# EspDetElet.net
KiCad netlist of a schematic drawn in EAGLE
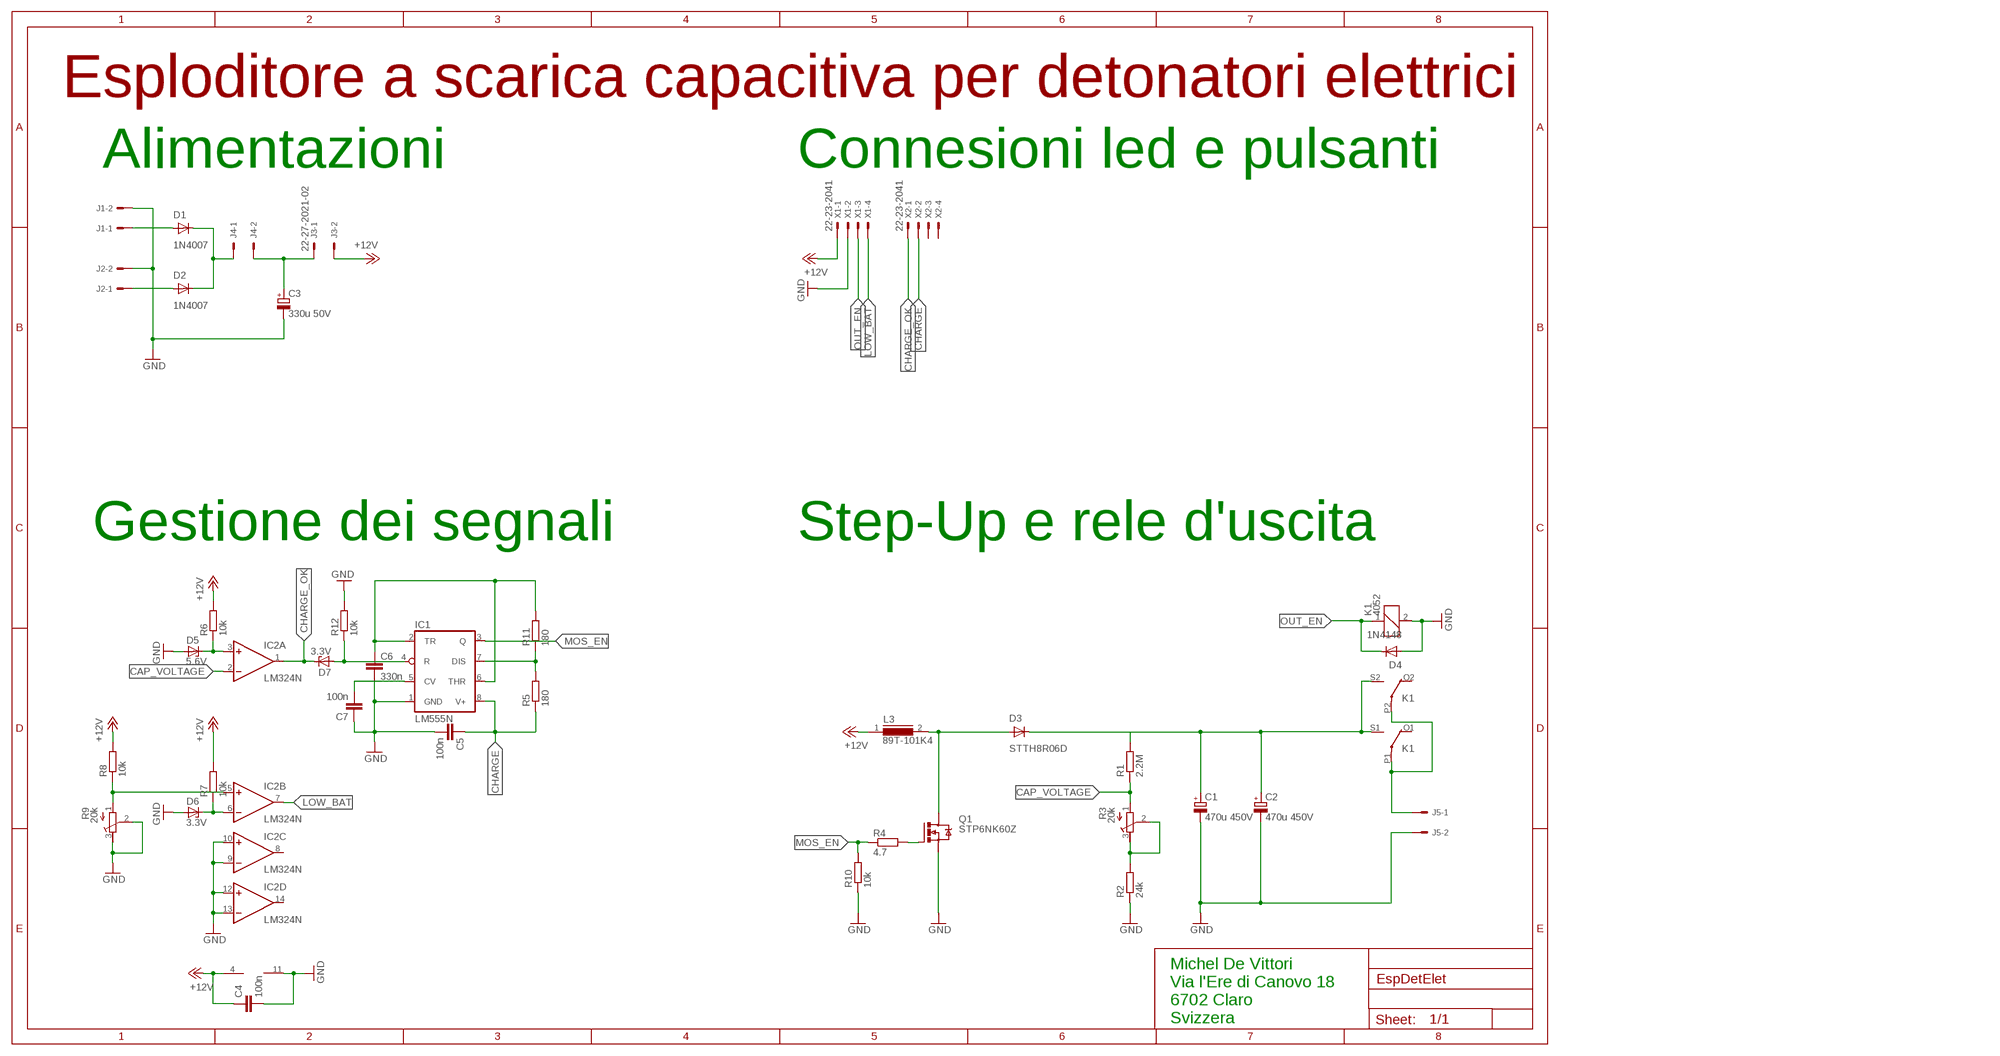
[diagram p0: schematic, sheet 1]

(export (version "E")
  (design (tool "Eeschema 10.0.6"))
  (components
    (comp (ref "C1")
      (value "470u 450V")
      (footprint "eagle-import:EB30D")
      (libsource (lib "eagle-import") (part "CPOL-EUE10-30"))
    )
    (comp (ref "C2")
      (value "470u 450V")
      (footprint "eagle-import:EB30D")
      (libsource (lib "eagle-import") (part "CPOL-EUE10-30"))
    )
    (comp (ref "C3")
      (value "330u 50V")
      (footprint "eagle-import:E5-10,5")
      (libsource (lib "eagle-import") (part "CPOL-EUE5-10.5"))
    )
    (comp (ref "C4")
      (value "100n")
      (footprint "eagle-import:C025-025X050")
      (libsource (lib "eagle-import") (part "C-EU025-025X050"))
    )
    (comp (ref "C5")
      (value "100n")
      (footprint "eagle-import:C025-025X050")
      (libsource (lib "eagle-import") (part "C-EU025-025X050"))
    )
    (comp (ref "C6")
      (value "330n")
      (footprint "eagle-import:C050-030X075")
      (libsource (lib "eagle-import") (part "C-EU050-030X075"))
    )
    (comp (ref "C7")
      (value "100n")
      (footprint "eagle-import:C025-025X050")
      (libsource (lib "eagle-import") (part "C-EU025-025X050"))
    )
    (comp (ref "D1")
      (value "1N4007")
      (footprint "eagle-import:DO41-10")
      (libsource (lib "eagle-import") (part "1N4004"))
    )
    (comp (ref "D2")
      (value "1N4007")
      (footprint "eagle-import:DO41-10")
      (libsource (lib "eagle-import") (part "1N4004"))
    )
    (comp (ref "D3")
      (value "STTH8R06D")
      (footprint "eagle-import:TO220ACS")
      (libsource (lib "eagle-import") (part "BYT08P"))
    )
    (comp (ref "D4")
      (value "1N4148")
      (footprint "eagle-import:DO35-7")
      (libsource (lib "eagle-import") (part "1N4148DO35-7"))
    )
    (comp (ref "D5")
      (value "5.6V")
      (footprint "eagle-import:ZDIO-7.5")
      (libsource (lib "eagle-import") (part "ZENER-DIODEZD-7.5"))
    )
    (comp (ref "D6")
      (value "3.3V")
      (footprint "eagle-import:ZDIO-7.5")
      (libsource (lib "eagle-import") (part "ZENER-DIODEZD-7.5"))
    )
    (comp (ref "D7")
      (value "3.3V")
      (footprint "eagle-import:ZDIO-7.5")
      (libsource (lib "eagle-import") (part "ZENER-DIODEZD-7.5"))
    )
    (comp (ref "IC1")
      (value "LM555N")
      (footprint "eagle-import:DIL08")
      (libsource (lib "eagle-import") (part "555NLM"))
    )
    (comp (ref "IC2")
      (value "LM324N")
      (footprint "eagle-import:DIL14")
      (libsource (lib "eagle-import") (part "LM324N"))
    )
    (comp (ref "J1")
      (value "KK-156-2")
      (footprint "eagle-import:KK-156-2")
      (libsource (lib "eagle-import") (part "KK-156-2"))
    )
    (comp (ref "J2")
      (value "KK-156-2")
      (footprint "eagle-import:KK-156-2")
      (libsource (lib "eagle-import") (part "KK-156-2"))
    )
    (comp (ref "J3")
      (value "22-27-2021-02")
      (footprint "eagle-import:6410-02")
      (libsource (lib "eagle-import") (part "22-?-0227-2021"))
    )
    (comp (ref "J4")
      (value "KK-156-2")
      (footprint "eagle-import:KK-156-2")
      (libsource (lib "eagle-import") (part "KK-156-2"))
    )
    (comp (ref "J5")
      (value "KK-156-2")
      (footprint "eagle-import:KK-156-2")
      (libsource (lib "eagle-import") (part "KK-156-2"))
    )
    (comp (ref "K1")
      (value "4052")
      (footprint "eagle-import:F4052")
      (libsource (lib "eagle-import") (part "4052"))
    )
    (comp (ref "L3")
      (value "89T-101K4")
      (footprint "eagle-import:SFT1030")
      (libsource (lib "eagle-import") (part "SFT1030"))
    )
    (comp (ref "Q1")
      (value "STP6NK60Z")
      (footprint "eagle-import:TO220BV")
      (libsource (lib "eagle-import") (part "STP5NA50"))
    )
    (comp (ref "R1")
      (value "2.2M")
      (footprint "eagle-import:0207_10")
      (libsource (lib "eagle-import") (part "R-EU_0207/10"))
    )
    (comp (ref "R2")
      (value "24k")
      (footprint "eagle-import:0207_10")
      (libsource (lib "eagle-import") (part "R-EU_0207/10"))
    )
    (comp (ref "R3")
      (value "20k")
      (footprint "eagle-import:RTRIM64W")
      (libsource (lib "eagle-import") (part "R-TRIMM64W"))
    )
    (comp (ref "R4")
      (value "4.7")
      (footprint "eagle-import:0207_10")
      (libsource (lib "eagle-import") (part "R-EU_0207/10"))
    )
    (comp (ref "R5")
      (value "180")
      (footprint "eagle-import:0207_10")
      (libsource (lib "eagle-import") (part "R-EU_0207/10"))
    )
    (comp (ref "R6")
      (value "10k")
      (footprint "eagle-import:0207_10")
      (libsource (lib "eagle-import") (part "R-EU_0207/10"))
    )
    (comp (ref "R7")
      (value "10k")
      (footprint "eagle-import:0207_10")
      (libsource (lib "eagle-import") (part "R-EU_0207/10"))
    )
    (comp (ref "R8")
      (value "10k")
      (footprint "eagle-import:0207_10")
      (libsource (lib "eagle-import") (part "R-EU_0207/10"))
    )
    (comp (ref "R9")
      (value "20k")
      (footprint "eagle-import:RTRIM64W")
      (libsource (lib "eagle-import") (part "R-TRIMM64W"))
    )
    (comp (ref "R10")
      (value "10k")
      (footprint "eagle-import:0207_10")
      (libsource (lib "eagle-import") (part "R-EU_0207/10"))
    )
    (comp (ref "R11")
      (value "180")
      (footprint "eagle-import:0207_10")
      (libsource (lib "eagle-import") (part "R-EU_0207/10"))
    )
    (comp (ref "R12")
      (value "10k")
      (footprint "eagle-import:0207_10")
      (libsource (lib "eagle-import") (part "R-EU_0207/10"))
    )
    (comp (ref "X1")
      (value "22-23-2041")
      (footprint "eagle-import:22-23-2041")
      (fields (field (name "MF") "MOLEX"))
      (libsource (lib "eagle-import") (part "22-23-2041"))
    )
    (comp (ref "X2")
      (value "22-23-2041")
      (footprint "eagle-import:22-23-2041")
      (fields (field (name "MF") "MOLEX"))
      (libsource (lib "eagle-import") (part "22-23-2041"))
    )
  )
  (nets
    (net (code "1") (name "+12V") (class "Default")
      (node (ref "C4") (pin "1") (pinfunction "1_1") (pintype "passive"))
      (node (ref "IC2") (pin "4") (pinfunction "V+_4") (pintype "power_in"))
      (node (ref "J3") (pin "2") (pinfunction "S_2") (pintype "passive"))
      (node (ref "L3") (pin "1") (pinfunction "1_1") (pintype "passive"))
      (node (ref "R6") (pin "2") (pinfunction "2_2") (pintype "passive"))
      (node (ref "R7") (pin "2") (pinfunction "2_2") (pintype "passive"))
      (node (ref "R8") (pin "2") (pinfunction "2_2") (pintype "passive"))
      (node (ref "X1") (pin "1") (pinfunction "S_1") (pintype "passive"))
    )
    (net (code "2") (name "CAP_VOLTAGE") (class "Default")
      (node (ref "IC2") (pin "2") (pinfunction "-IN_2") (pintype "input"))
      (node (ref "R1") (pin "1") (pinfunction "1_1") (pintype "passive"))
      (node (ref "R3") (pin "1") (pinfunction "E_1") (pintype "passive"))
    )
    (net (code "3") (name "CHARGE") (class "Default")
      (node (ref "C5") (pin "1") (pinfunction "1_1") (pintype "passive"))
      (node (ref "IC1") (pin "8") (pinfunction "V+_8") (pintype "power_in"))
      (node (ref "R5") (pin "1") (pinfunction "1_1") (pintype "passive"))
      (node (ref "X2") (pin "2") (pinfunction "S_2") (pintype "passive"))
    )
    (net (code "4") (name "CHARGE_OK") (class "Default")
      (node (ref "D7") (pin "C") (pinfunction "C_C") (pintype "passive"))
      (node (ref "IC2") (pin "1") (pinfunction "OUT_1") (pintype "output"))
      (node (ref "X2") (pin "1") (pinfunction "S_1") (pintype "passive"))
    )
    (net (code "5") (name "GND") (class "Default")
      (node (ref "C1") (pin "-") (pinfunction "-_-") (pintype "passive"))
      (node (ref "C2") (pin "-") (pinfunction "-_-") (pintype "passive"))
      (node (ref "C3") (pin "-") (pinfunction "-_-") (pintype "passive"))
      (node (ref "C4") (pin "2") (pinfunction "2_2") (pintype "passive"))
      (node (ref "C5") (pin "2") (pinfunction "2_2") (pintype "passive"))
      (node (ref "C6") (pin "2") (pinfunction "2_2") (pintype "passive"))
      (node (ref "C7") (pin "1") (pinfunction "1_1") (pintype "passive"))
      (node (ref "D4") (pin "A") (pinfunction "A_A") (pintype "passive"))
      (node (ref "D5") (pin "A") (pinfunction "A_A") (pintype "passive"))
      (node (ref "D6") (pin "A") (pinfunction "A_A") (pintype "passive"))
      (node (ref "IC1") (pin "1") (pinfunction "GND_1") (pintype "power_in"))
      (node (ref "IC2") (pin "10") (pinfunction "+IN_10") (pintype "input"))
      (node (ref "IC2") (pin "11") (pinfunction "V-_11") (pintype "power_in"))
      (node (ref "IC2") (pin "12") (pinfunction "+IN_12") (pintype "input"))
      (node (ref "IC2") (pin "13") (pinfunction "-IN_13") (pintype "input"))
      (node (ref "IC2") (pin "9") (pinfunction "-IN_9") (pintype "input"))
      (node (ref "J1") (pin "2") (pinfunction "S_2") (pintype "passive"))
      (node (ref "J2") (pin "2") (pinfunction "S_2") (pintype "passive"))
      (node (ref "J5") (pin "2") (pinfunction "S_2") (pintype "passive"))
      (node (ref "K1") (pin "2") (pinfunction "2_2") (pintype "passive"))
      (node (ref "Q1") (pin "S") (pinfunction "S_S") (pintype "passive"))
      (node (ref "R10") (pin "1") (pinfunction "1_1") (pintype "passive"))
      (node (ref "R12") (pin "2") (pinfunction "2_2") (pintype "passive"))
      (node (ref "R2") (pin "1") (pinfunction "1_1") (pintype "passive"))
      (node (ref "R9") (pin "2") (pinfunction "S_2") (pintype "passive"))
      (node (ref "R9") (pin "3") (pinfunction "A_3") (pintype "passive"))
      (node (ref "X1") (pin "2") (pinfunction "S_2") (pintype "passive"))
    )
    (net (code "6") (name "LOW_BAT") (class "Default")
      (node (ref "IC2") (pin "7") (pinfunction "OUT_7") (pintype "output"))
      (node (ref "X1") (pin "4") (pinfunction "S_4") (pintype "passive"))
    )
    (net (code "7") (name "MOS_EN") (class "Default")
      (node (ref "IC1") (pin "3") (pinfunction "Q_3") (pintype "output"))
      (node (ref "R10") (pin "2") (pinfunction "2_2") (pintype "passive"))
      (node (ref "R4") (pin "1") (pinfunction "1_1") (pintype "passive"))
    )
    (net (code "8") (name "Net-(D3-PadA)") (class "Default")
      (node (ref "D3") (pin "A") (pinfunction "A_A") (pintype "passive"))
      (node (ref "L3") (pin "2") (pinfunction "2_2") (pintype "passive"))
      (node (ref "Q1") (pin "D") (pinfunction "D_D") (pintype "passive"))
    )
    (net (code "9") (name "Net-(IC1-CV)") (class "Default")
      (node (ref "C7") (pin "2") (pinfunction "2_2") (pintype "passive"))
      (node (ref "IC1") (pin "5") (pinfunction "CV_5") (pintype "input"))
    )
    (net (code "10") (name "Net-(IC1-DIS)") (class "Default")
      (node (ref "IC1") (pin "7") (pinfunction "DIS_7") (pintype "input"))
      (node (ref "R11") (pin "1") (pinfunction "1_1") (pintype "passive"))
      (node (ref "R5") (pin "2") (pinfunction "2_2") (pintype "passive"))
    )
    (net (code "11") (name "Net-(IC1-R)") (class "Default")
      (node (ref "D7") (pin "A") (pinfunction "A_A") (pintype "passive"))
      (node (ref "IC1") (pin "4") (pinfunction "R_4") (pintype "input"))
      (node (ref "R12") (pin "1") (pinfunction "1_1") (pintype "passive"))
    )
    (net (code "12") (name "Net-(IC1-THR)") (class "Default")
      (node (ref "C6") (pin "1") (pinfunction "1_1") (pintype "passive"))
      (node (ref "IC1") (pin "2") (pinfunction "TR_2") (pintype "input"))
      (node (ref "IC1") (pin "6") (pinfunction "THR_6") (pintype "input"))
      (node (ref "R11") (pin "2") (pinfunction "2_2") (pintype "passive"))
    )
    (net (code "13") (name "Net-(IC2A-+IN)") (class "Default")
      (node (ref "D5") (pin "C") (pinfunction "C_C") (pintype "passive"))
      (node (ref "IC2") (pin "3") (pinfunction "+IN_3") (pintype "input"))
      (node (ref "R6") (pin "1") (pinfunction "1_1") (pintype "passive"))
    )
    (net (code "14") (name "Net-(IC2B-+IN)") (class "Default")
      (node (ref "IC2") (pin "5") (pinfunction "+IN_5") (pintype "input"))
      (node (ref "R8") (pin "1") (pinfunction "1_1") (pintype "passive"))
      (node (ref "R9") (pin "1") (pinfunction "E_1") (pintype "passive"))
    )
    (net (code "15") (name "Net-(IC2B--IN)") (class "Default")
      (node (ref "D6") (pin "C") (pinfunction "C_C") (pintype "passive"))
      (node (ref "IC2") (pin "6") (pinfunction "-IN_6") (pintype "input"))
      (node (ref "R7") (pin "1") (pinfunction "1_1") (pintype "passive"))
    )
    (net (code "16") (name "Net-(J1A-S)") (class "Default")
      (node (ref "D1") (pin "A") (pinfunction "A_A") (pintype "passive"))
      (node (ref "J1") (pin "1") (pinfunction "S_1") (pintype "passive"))
    )
    (net (code "17") (name "Net-(J2A-S)") (class "Default")
      (node (ref "D2") (pin "A") (pinfunction "A_A") (pintype "passive"))
      (node (ref "J2") (pin "1") (pinfunction "S_1") (pintype "passive"))
    )
    (net (code "18") (name "Net-(J3A-S)") (class "Default")
      (node (ref "C3") (pin "+") (pinfunction "+_+") (pintype "passive"))
      (node (ref "J3") (pin "1") (pinfunction "S_1") (pintype "passive"))
      (node (ref "J4") (pin "2") (pinfunction "S_2") (pintype "passive"))
    )
    (net (code "19") (name "Net-(J4A-S)") (class "Default")
      (node (ref "D1") (pin "C") (pinfunction "C_C") (pintype "passive"))
      (node (ref "D2") (pin "C") (pinfunction "C_C") (pintype "passive"))
      (node (ref "J4") (pin "1") (pinfunction "S_1") (pintype "passive"))
    )
    (net (code "20") (name "Net-(J5A-S)") (class "Default")
      (node (ref "J5") (pin "1") (pinfunction "S_1") (pintype "passive"))
      (node (ref "K1") (pin "P1") (pinfunction "P_P1") (pintype "passive"))
      (node (ref "K1") (pin "P2") (pinfunction "P_P2") (pintype "passive"))
    )
    (net (code "21") (name "Net-(K1B-S)") (class "Default")
      (node (ref "C1") (pin "+") (pinfunction "+_+") (pintype "passive"))
      (node (ref "C2") (pin "+") (pinfunction "+_+") (pintype "passive"))
      (node (ref "D3") (pin "C") (pinfunction "C_C") (pintype "passive"))
      (node (ref "K1") (pin "S1") (pinfunction "S_S1") (pintype "passive"))
      (node (ref "K1") (pin "S2") (pinfunction "S_S2") (pintype "passive"))
      (node (ref "R1") (pin "2") (pinfunction "2_2") (pintype "passive"))
    )
    (net (code "22") (name "Net-(Q1-PadG)") (class "Default")
      (node (ref "Q1") (pin "G") (pinfunction "G_G") (pintype "passive"))
      (node (ref "R4") (pin "2") (pinfunction "2_2") (pintype "passive"))
    )
    (net (code "23") (name "Net-(R3-A)") (class "Default")
      (node (ref "R2") (pin "2") (pinfunction "2_2") (pintype "passive"))
      (node (ref "R3") (pin "2") (pinfunction "S_2") (pintype "passive"))
      (node (ref "R3") (pin "3") (pinfunction "A_3") (pintype "passive"))
    )
    (net (code "24") (name "OUT_EN") (class "Default")
      (node (ref "D4") (pin "C") (pinfunction "C_C") (pintype "passive"))
      (node (ref "K1") (pin "1") (pinfunction "1_1") (pintype "passive"))
      (node (ref "X1") (pin "3") (pinfunction "S_3") (pintype "passive"))
    )
    (net (code "25") (name "unconnected-(IC2C-OUT-Pad8)") (class "Default")
      (node (ref "IC2") (pin "8") (pinfunction "OUT_8") (pintype "output"))
    )
    (net (code "26") (name "unconnected-(IC2D-OUT-Pad14)") (class "Default")
      (node (ref "IC2") (pin "14") (pinfunction "OUT_14") (pintype "output"))
    )
    (net (code "27") (name "unconnected-(K1B-O-PadO1)") (class "Default")
      (node (ref "K1") (pin "O1") (pinfunction "O_O1") (pintype "passive"))
    )
    (net (code "28") (name "unconnected-(K1C-O-PadO2)") (class "Default")
      (node (ref "K1") (pin "O2") (pinfunction "O_O2") (pintype "passive"))
    )
    (net (code "29") (name "unconnected-(X2C-S-Pad3)") (class "Default")
      (node (ref "X2") (pin "3") (pinfunction "S_3") (pintype "passive"))
    )
    (net (code "30") (name "unconnected-(X2D-S-Pad4)") (class "Default")
      (node (ref "X2") (pin "4") (pinfunction "S_4") (pintype "passive"))
    )
  )
)
